# isp_hvp_shield.net
KiCad netlist of a schematic drawn in EAGLE
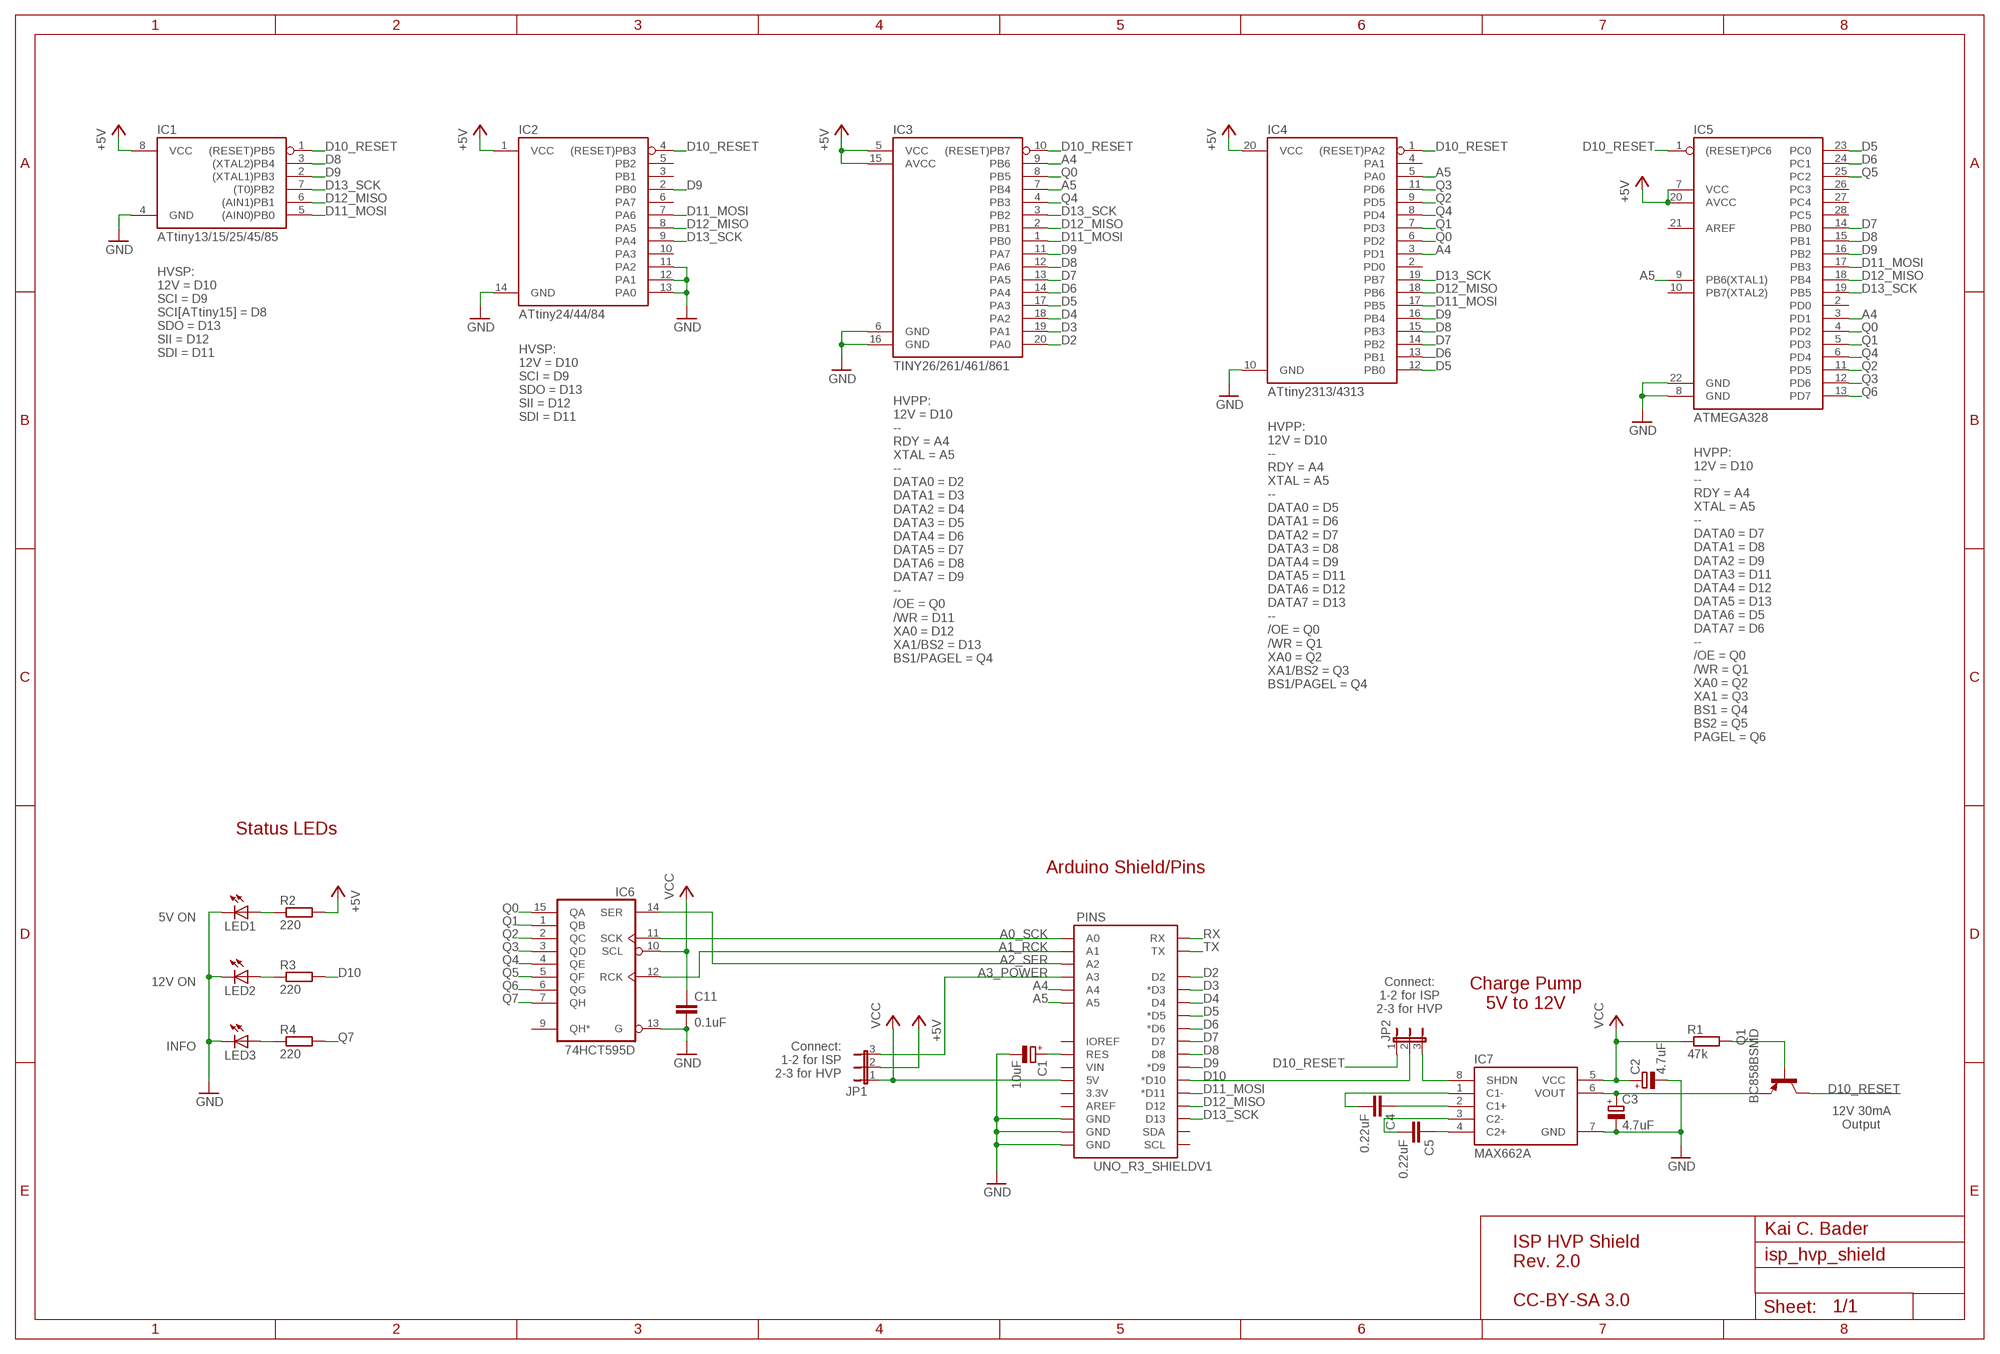
[diagram p0: schematic, sheet 1]

(export (version "E")
  (design (tool "Eeschema 10.0.6"))
  (components
    (comp (ref "C1")
      (value "10uF")
      (footprint "eagle-import:E2-5")
      (libsource (lib "eagle-import") (part "CPOL-EUE2-5"))
    )
    (comp (ref "C2")
      (value "4.7uF")
      (footprint "eagle-import:E2-5")
      (libsource (lib "eagle-import") (part "CPOL-EUE2-5"))
    )
    (comp (ref "C3")
      (value "4.7uF")
      (footprint "eagle-import:E2-5")
      (libsource (lib "eagle-import") (part "CPOL-EUE2-5"))
    )
    (comp (ref "C4")
      (value "0.22uF")
      (footprint "eagle-import:C0805")
      (libsource (lib "eagle-import") (part "C-EUC0805"))
    )
    (comp (ref "C5")
      (value "0.22uF")
      (footprint "eagle-import:C0805")
      (libsource (lib "eagle-import") (part "C-EUC0805"))
    )
    (comp (ref "C11")
      (value "0.1uF")
      (footprint "eagle-import:C0805")
      (libsource (lib "eagle-import") (part "C-EUC0805"))
    )
    (comp (ref "IC1")
      (value "ATtiny13/15/25/45/85")
      (footprint "eagle-import:DIL08")
      (libsource (lib "eagle-import") (part "TINY85P"))
    )
    (comp (ref "IC2")
      (value "ATtiny24/44/84")
      (footprint "eagle-import:DIL14")
      (libsource (lib "eagle-import") (part "TINY84"))
    )
    (comp (ref "IC3")
      (value "TINY26/261/461/861")
      (footprint "eagle-import:DIL20")
      (libsource (lib "eagle-import") (part "TINY26"))
    )
    (comp (ref "IC4")
      (value "ATtiny2313/4313")
      (footprint "eagle-import:DIL20")
      (libsource (lib "eagle-import") (part "TINY2313"))
    )
    (comp (ref "IC5")
      (value "ATMEGA328")
      (footprint "eagle-import:DIL28")
      (libsource (lib "eagle-import") (part "ATMEGA328"))
    )
    (comp (ref "IC6")
      (value "74HCT595D")
      (footprint "eagle-import:SO16")
      (libsource (lib "eagle-import") (part "74595DHCT"))
    )
    (comp (ref "IC7")
      (value "MAX662A")
      (footprint "eagle-import:SO08")
      (libsource (lib "eagle-import") (part "MAX662A"))
    )
    (comp (ref "JP1")
      (value "JP2E")
      (footprint "eagle-import:JP2")
      (libsource (lib "eagle-import") (part "JP2E"))
    )
    (comp (ref "JP2")
      (value "JP2E")
      (footprint "eagle-import:JP2")
      (libsource (lib "eagle-import") (part "JP2E"))
    )
    (comp (ref "LED1")
      (value "LEDCHIPLED_0805")
      (footprint "eagle-import:CHIPLED_0805")
      (libsource (lib "eagle-import") (part "LEDCHIPLED_0805"))
    )
    (comp (ref "LED2")
      (value "LEDCHIPLED_0805")
      (footprint "eagle-import:CHIPLED_0805")
      (libsource (lib "eagle-import") (part "LEDCHIPLED_0805"))
    )
    (comp (ref "LED3")
      (value "LEDCHIPLED_0805")
      (footprint "eagle-import:CHIPLED_0805")
      (libsource (lib "eagle-import") (part "LEDCHIPLED_0805"))
    )
    (comp (ref "PINS")
      (value "UNO_R3_SHIELDV1")
      (footprint "eagle-import:UNO_R3_SHIELD")
      (libsource (lib "eagle-import") (part "UNO_R3_SHIELDV1"))
    )
    (comp (ref "Q1")
      (value "BC858BSMD")
      (footprint "eagle-import:SOT23-BEC")
      (libsource (lib "eagle-import") (part "BC858SMDB"))
    )
    (comp (ref "R1")
      (value "47k")
      (footprint "eagle-import:R0805")
      (libsource (lib "eagle-import") (part "R-EU_R0805"))
    )
    (comp (ref "R2")
      (value "220")
      (footprint "eagle-import:R0805")
      (libsource (lib "eagle-import") (part "R-EU_R0805"))
    )
    (comp (ref "R3")
      (value "220")
      (footprint "eagle-import:R0805")
      (libsource (lib "eagle-import") (part "R-EU_R0805"))
    )
    (comp (ref "R4")
      (value "220")
      (footprint "eagle-import:R0805")
      (libsource (lib "eagle-import") (part "R-EU_R0805"))
    )
  )
  (nets
    (net (code "1") (name "+5V") (class "Default")
      (node (ref "IC1") (pin "8") (pinfunction "VCC_8") (pintype "power_in"))
      (node (ref "IC2") (pin "1") (pinfunction "VCC_1") (pintype "power_in"))
      (node (ref "IC3") (pin "15") (pinfunction "AVCC_15") (pintype "power_in"))
      (node (ref "IC3") (pin "5") (pinfunction "VCC_5") (pintype "power_in"))
      (node (ref "IC4") (pin "20") (pinfunction "VCC_20") (pintype "power_in"))
      (node (ref "IC5") (pin "20") (pinfunction "AVCC_20") (pintype "power_in"))
      (node (ref "IC5") (pin "7") (pinfunction "VCC_7") (pintype "power_in"))
      (node (ref "JP1") (pin "2") (pinfunction "2_2") (pintype "passive"))
      (node (ref "R2") (pin "2") (pinfunction "2_2") (pintype "passive"))
    )
    (net (code "2") (name "/A0_SCK") (class "Default")
      (node (ref "IC6") (pin "11") (pinfunction "SCK_11") (pintype "input"))
      (node (ref "PINS") (pin "A0") (pinfunction "A0_A0") (pintype "bidirectional"))
    )
    (net (code "3") (name "/A1_RCK") (class "Default")
      (node (ref "IC6") (pin "12") (pinfunction "RCK_12") (pintype "input"))
      (node (ref "PINS") (pin "A1") (pinfunction "A1_A1") (pintype "bidirectional"))
    )
    (net (code "4") (name "/A2_SER") (class "Default")
      (node (ref "IC6") (pin "14") (pinfunction "SER_14") (pintype "input"))
      (node (ref "PINS") (pin "A2") (pinfunction "A2_A2") (pintype "bidirectional"))
    )
    (net (code "5") (name "/A3_POWER") (class "Default")
      (node (ref "JP1") (pin "3") (pinfunction "3_3") (pintype "passive"))
      (node (ref "PINS") (pin "A3") (pinfunction "A3_A3") (pintype "bidirectional"))
    )
    (net (code "6") (name "/A4") (class "Default")
      (node (ref "IC3") (pin "9") (pinfunction "PB6_9") (pintype "bidirectional"))
      (node (ref "IC4") (pin "3") (pinfunction "PD1_3") (pintype "bidirectional"))
      (node (ref "IC5") (pin "3") (pinfunction "PD1_3") (pintype "bidirectional"))
      (node (ref "PINS") (pin "A4") (pinfunction "A4_A4") (pintype "bidirectional"))
    )
    (net (code "7") (name "/A5") (class "Default")
      (node (ref "IC3") (pin "7") (pinfunction "PB4_7") (pintype "bidirectional"))
      (node (ref "IC4") (pin "5") (pinfunction "PA0_5") (pintype "bidirectional"))
      (node (ref "IC5") (pin "9") (pinfunction "PB6(XTAL1)_9") (pintype "bidirectional"))
      (node (ref "PINS") (pin "A5") (pinfunction "A5_A5") (pintype "bidirectional"))
    )
    (net (code "8") (name "/AREF") (class "Default")
      (node (ref "IC5") (pin "21") (pinfunction "AREF_21") (pintype "power_in"))
    )
    (net (code "9") (name "/D2") (class "Default")
      (node (ref "IC3") (pin "20") (pinfunction "PA0_20") (pintype "bidirectional"))
      (node (ref "PINS") (pin "D2") (pinfunction "D2_D2") (pintype "bidirectional"))
    )
    (net (code "10") (name "/D3") (class "Default")
      (node (ref "IC3") (pin "19") (pinfunction "PA1_19") (pintype "bidirectional"))
      (node (ref "PINS") (pin "D3") (pinfunction "*D3_D3") (pintype "bidirectional"))
    )
    (net (code "11") (name "/D4") (class "Default")
      (node (ref "IC3") (pin "18") (pinfunction "PA2_18") (pintype "bidirectional"))
      (node (ref "PINS") (pin "D4") (pinfunction "D4_D4") (pintype "bidirectional"))
    )
    (net (code "12") (name "/D5") (class "Default")
      (node (ref "IC3") (pin "17") (pinfunction "PA3_17") (pintype "bidirectional"))
      (node (ref "IC4") (pin "12") (pinfunction "PB0_12") (pintype "bidirectional"))
      (node (ref "IC5") (pin "23") (pinfunction "PC0_23") (pintype "bidirectional"))
      (node (ref "PINS") (pin "D5") (pinfunction "*D5_D5") (pintype "bidirectional"))
    )
    (net (code "13") (name "/D6") (class "Default")
      (node (ref "IC3") (pin "14") (pinfunction "PA4_14") (pintype "bidirectional"))
      (node (ref "IC4") (pin "13") (pinfunction "PB1_13") (pintype "bidirectional"))
      (node (ref "IC5") (pin "24") (pinfunction "PC1_24") (pintype "bidirectional"))
      (node (ref "PINS") (pin "D6") (pinfunction "*D6_D6") (pintype "bidirectional"))
    )
    (net (code "14") (name "/D7") (class "Default")
      (node (ref "IC3") (pin "13") (pinfunction "PA5_13") (pintype "bidirectional"))
      (node (ref "IC4") (pin "14") (pinfunction "PB2_14") (pintype "bidirectional"))
      (node (ref "IC5") (pin "14") (pinfunction "PB0_14") (pintype "bidirectional"))
      (node (ref "PINS") (pin "D7") (pinfunction "D7_D7") (pintype "bidirectional"))
    )
    (net (code "15") (name "/D8") (class "Default")
      (node (ref "IC1") (pin "3") (pinfunction "(XTAL2)PB4_3") (pintype "bidirectional"))
      (node (ref "IC3") (pin "12") (pinfunction "PA6_12") (pintype "bidirectional"))
      (node (ref "IC4") (pin "15") (pinfunction "PB3_15") (pintype "bidirectional"))
      (node (ref "IC5") (pin "15") (pinfunction "PB1_15") (pintype "bidirectional"))
      (node (ref "PINS") (pin "D8") (pinfunction "D8_D8") (pintype "bidirectional"))
    )
    (net (code "16") (name "/D9") (class "Default")
      (node (ref "IC1") (pin "2") (pinfunction "(XTAL1)PB3_2") (pintype "bidirectional"))
      (node (ref "IC2") (pin "2") (pinfunction "PB0_2") (pintype "bidirectional"))
      (node (ref "IC3") (pin "11") (pinfunction "PA7_11") (pintype "bidirectional"))
      (node (ref "IC4") (pin "16") (pinfunction "PB4_16") (pintype "bidirectional"))
      (node (ref "IC5") (pin "16") (pinfunction "PB2_16") (pintype "bidirectional"))
      (node (ref "PINS") (pin "D9") (pinfunction "*D9_D9") (pintype "bidirectional"))
    )
    (net (code "17") (name "/D10") (class "Default")
      (node (ref "JP2") (pin "2") (pinfunction "2_2") (pintype "passive"))
      (node (ref "PINS") (pin "D10") (pinfunction "*D10_D10") (pintype "bidirectional"))
      (node (ref "R3") (pin "2") (pinfunction "2_2") (pintype "passive"))
    )
    (net (code "18") (name "/D10_RESET") (class "Default")
      (node (ref "IC1") (pin "1") (pinfunction "(RESET)PB5_1") (pintype "bidirectional"))
      (node (ref "IC2") (pin "4") (pinfunction "(RESET)PB3_4") (pintype "bidirectional"))
      (node (ref "IC3") (pin "10") (pinfunction "(RESET)PB7_10") (pintype "bidirectional"))
      (node (ref "IC4") (pin "1") (pinfunction "(RESET)PA2_1") (pintype "bidirectional"))
      (node (ref "IC5") (pin "1") (pinfunction "(RESET)PC6_1") (pintype "bidirectional"))
      (node (ref "JP2") (pin "1") (pinfunction "1_1") (pintype "passive"))
      (node (ref "Q1") (pin "C") (pinfunction "C_C") (pintype "passive"))
    )
    (net (code "19") (name "/D11_MOSI") (class "Default")
      (node (ref "IC1") (pin "5") (pinfunction "(AIN0)PB0_5") (pintype "bidirectional"))
      (node (ref "IC2") (pin "7") (pinfunction "PA6_7") (pintype "bidirectional"))
      (node (ref "IC3") (pin "1") (pinfunction "PB0_1") (pintype "bidirectional"))
      (node (ref "IC4") (pin "17") (pinfunction "PB5_17") (pintype "bidirectional"))
      (node (ref "IC5") (pin "17") (pinfunction "PB3_17") (pintype "bidirectional"))
      (node (ref "PINS") (pin "D11") (pinfunction "*D11_D11") (pintype "bidirectional"))
    )
    (net (code "20") (name "/D12_MISO") (class "Default")
      (node (ref "IC1") (pin "6") (pinfunction "(AIN1)PB1_6") (pintype "bidirectional"))
      (node (ref "IC2") (pin "8") (pinfunction "PA5_8") (pintype "bidirectional"))
      (node (ref "IC3") (pin "2") (pinfunction "PB1_2") (pintype "bidirectional"))
      (node (ref "IC4") (pin "18") (pinfunction "PB6_18") (pintype "bidirectional"))
      (node (ref "IC5") (pin "18") (pinfunction "PB4_18") (pintype "bidirectional"))
      (node (ref "PINS") (pin "D12") (pinfunction "D12_D12") (pintype "bidirectional"))
    )
    (net (code "21") (name "/D13_SCK") (class "Default")
      (node (ref "IC1") (pin "7") (pinfunction "(T0)PB2_7") (pintype "bidirectional"))
      (node (ref "IC2") (pin "9") (pinfunction "PA4_9") (pintype "bidirectional"))
      (node (ref "IC3") (pin "3") (pinfunction "PB2_3") (pintype "bidirectional"))
      (node (ref "IC4") (pin "19") (pinfunction "PB7_19") (pintype "bidirectional"))
      (node (ref "IC5") (pin "19") (pinfunction "PB5_19") (pintype "bidirectional"))
      (node (ref "PINS") (pin "D13") (pinfunction "D13_D13") (pintype "bidirectional"))
    )
    (net (code "22") (name "/Q0") (class "Default")
      (node (ref "IC3") (pin "8") (pinfunction "PB5_8") (pintype "bidirectional"))
      (node (ref "IC4") (pin "6") (pinfunction "PD2_6") (pintype "bidirectional"))
      (node (ref "IC5") (pin "4") (pinfunction "PD2_4") (pintype "bidirectional"))
      (node (ref "IC6") (pin "15") (pinfunction "QA_15") (pintype "tri_state"))
    )
    (net (code "23") (name "/Q1") (class "Default")
      (node (ref "IC4") (pin "7") (pinfunction "PD3_7") (pintype "bidirectional"))
      (node (ref "IC5") (pin "5") (pinfunction "PD3_5") (pintype "bidirectional"))
      (node (ref "IC6") (pin "1") (pinfunction "QB_1") (pintype "tri_state"))
    )
    (net (code "24") (name "/Q2") (class "Default")
      (node (ref "IC4") (pin "9") (pinfunction "PD5_9") (pintype "bidirectional"))
      (node (ref "IC5") (pin "11") (pinfunction "PD5_11") (pintype "bidirectional"))
      (node (ref "IC6") (pin "2") (pinfunction "QC_2") (pintype "tri_state"))
    )
    (net (code "25") (name "/Q3") (class "Default")
      (node (ref "IC4") (pin "11") (pinfunction "PD6_11") (pintype "bidirectional"))
      (node (ref "IC5") (pin "12") (pinfunction "PD6_12") (pintype "bidirectional"))
      (node (ref "IC6") (pin "3") (pinfunction "QD_3") (pintype "tri_state"))
    )
    (net (code "26") (name "/Q4") (class "Default")
      (node (ref "IC3") (pin "4") (pinfunction "PB3_4") (pintype "bidirectional"))
      (node (ref "IC4") (pin "8") (pinfunction "PD4_8") (pintype "bidirectional"))
      (node (ref "IC5") (pin "6") (pinfunction "PD4_6") (pintype "bidirectional"))
      (node (ref "IC6") (pin "4") (pinfunction "QE_4") (pintype "tri_state"))
    )
    (net (code "27") (name "/Q5") (class "Default")
      (node (ref "IC5") (pin "25") (pinfunction "PC2_25") (pintype "bidirectional"))
      (node (ref "IC6") (pin "5") (pinfunction "QF_5") (pintype "tri_state"))
    )
    (net (code "28") (name "/Q6") (class "Default")
      (node (ref "IC5") (pin "13") (pinfunction "PD7_13") (pintype "bidirectional"))
      (node (ref "IC6") (pin "6") (pinfunction "QG_6") (pintype "tri_state"))
    )
    (net (code "29") (name "/Q7") (class "Default")
      (node (ref "IC6") (pin "7") (pinfunction "QH_7") (pintype "tri_state"))
      (node (ref "R4") (pin "2") (pinfunction "2_2") (pintype "passive"))
    )
    (net (code "30") (name "/RX") (class "Default")
      (node (ref "PINS") (pin "RX") (pinfunction "RX_RX") (pintype "bidirectional"))
    )
    (net (code "31") (name "/TX") (class "Default")
      (node (ref "PINS") (pin "TX") (pinfunction "TX_TX") (pintype "bidirectional"))
    )
    (net (code "32") (name "GND") (class "Default")
      (node (ref "C1") (pin "-") (pinfunction "-_-") (pintype "passive"))
      (node (ref "C11") (pin "2") (pinfunction "2_2") (pintype "passive"))
      (node (ref "C2") (pin "-") (pinfunction "-_-") (pintype "passive"))
      (node (ref "C3") (pin "-") (pinfunction "-_-") (pintype "passive"))
      (node (ref "IC1") (pin "4") (pinfunction "GND_4") (pintype "power_in"))
      (node (ref "IC2") (pin "11") (pinfunction "PA2_11") (pintype "bidirectional"))
      (node (ref "IC2") (pin "12") (pinfunction "PA1_12") (pintype "bidirectional"))
      (node (ref "IC2") (pin "13") (pinfunction "PA0_13") (pintype "bidirectional"))
      (node (ref "IC2") (pin "14") (pinfunction "GND_14") (pintype "power_in"))
      (node (ref "IC3") (pin "16") (pinfunction "GND_16") (pintype "power_in"))
      (node (ref "IC3") (pin "6") (pinfunction "GND_6") (pintype "power_in"))
      (node (ref "IC4") (pin "10") (pinfunction "GND_10") (pintype "power_in"))
      (node (ref "IC5") (pin "22") (pinfunction "GND_22") (pintype "power_in"))
      (node (ref "IC5") (pin "8") (pinfunction "GND_8") (pintype "power_in"))
      (node (ref "IC6") (pin "13") (pinfunction "G_13") (pintype "input"))
      (node (ref "IC7") (pin "7") (pinfunction "GND_7") (pintype "power_in"))
      (node (ref "LED1") (pin "C") (pinfunction "C_C") (pintype "passive"))
      (node (ref "LED2") (pin "C") (pinfunction "C_C") (pintype "passive"))
      (node (ref "LED3") (pin "C") (pinfunction "C_C") (pintype "passive"))
      (node (ref "PINS") (pin "GND@0") (pinfunction "GND_GND@0") (pintype "bidirectional"))
      (node (ref "PINS") (pin "GND@1") (pinfunction "GND_GND@1") (pintype "bidirectional"))
      (node (ref "PINS") (pin "GND@2") (pinfunction "GND_GND@2") (pintype "bidirectional"))
    )
    (net (code "33") (name "Net-(C1-Pad+)") (class "Default")
      (node (ref "C1") (pin "+") (pinfunction "+_+") (pintype "passive"))
      (node (ref "PINS") (pin "RES") (pinfunction "RES_RES") (pintype "bidirectional"))
    )
    (net (code "34") (name "Net-(IC7-C1+)") (class "Default")
      (node (ref "C4") (pin "1") (pinfunction "1_1") (pintype "passive"))
      (node (ref "IC7") (pin "2") (pinfunction "C1+_2") (pintype "bidirectional"))
    )
    (net (code "35") (name "Net-(IC7-C1-)") (class "Default")
      (node (ref "C4") (pin "2") (pinfunction "2_2") (pintype "passive"))
      (node (ref "IC7") (pin "1") (pinfunction "C1-_1") (pintype "bidirectional"))
    )
    (net (code "36") (name "Net-(IC7-C2+)") (class "Default")
      (node (ref "C5") (pin "1") (pinfunction "1_1") (pintype "passive"))
      (node (ref "IC7") (pin "4") (pinfunction "C2+_4") (pintype "bidirectional"))
    )
    (net (code "37") (name "Net-(IC7-C2-)") (class "Default")
      (node (ref "C5") (pin "2") (pinfunction "2_2") (pintype "passive"))
      (node (ref "IC7") (pin "3") (pinfunction "C2-_3") (pintype "bidirectional"))
    )
    (net (code "38") (name "Net-(IC7-SHDN)") (class "Default")
      (node (ref "IC7") (pin "8") (pinfunction "SHDN_8") (pintype "input"))
      (node (ref "JP2") (pin "3") (pinfunction "3_3") (pintype "passive"))
    )
    (net (code "39") (name "Net-(IC7-VOUT)") (class "Default")
      (node (ref "C3") (pin "+") (pinfunction "+_+") (pintype "passive"))
      (node (ref "IC7") (pin "6") (pinfunction "VOUT_6") (pintype "power_in"))
      (node (ref "Q1") (pin "E") (pinfunction "E_E") (pintype "passive"))
    )
    (net (code "40") (name "Net-(LED1-PadA)") (class "Default")
      (node (ref "LED1") (pin "A") (pinfunction "A_A") (pintype "passive"))
      (node (ref "R2") (pin "1") (pinfunction "1_1") (pintype "passive"))
    )
    (net (code "41") (name "Net-(LED2-PadA)") (class "Default")
      (node (ref "LED2") (pin "A") (pinfunction "A_A") (pintype "passive"))
      (node (ref "R3") (pin "1") (pinfunction "1_1") (pintype "passive"))
    )
    (net (code "42") (name "Net-(LED3-PadA)") (class "Default")
      (node (ref "LED3") (pin "A") (pinfunction "A_A") (pintype "passive"))
      (node (ref "R4") (pin "1") (pinfunction "1_1") (pintype "passive"))
    )
    (net (code "43") (name "Net-(Q1-PadB)") (class "Default")
      (node (ref "Q1") (pin "B") (pinfunction "B_B") (pintype "passive"))
      (node (ref "R1") (pin "2") (pinfunction "2_2") (pintype "passive"))
    )
    (net (code "44") (name "VCC") (class "Default")
      (node (ref "C11") (pin "1") (pinfunction "1_1") (pintype "passive"))
      (node (ref "C2") (pin "+") (pinfunction "+_+") (pintype "passive"))
      (node (ref "IC6") (pin "10") (pinfunction "SCL_10") (pintype "input"))
      (node (ref "IC7") (pin "5") (pinfunction "VCC_5") (pintype "power_in"))
      (node (ref "JP1") (pin "1") (pinfunction "1_1") (pintype "passive"))
      (node (ref "PINS") (pin "5V") (pinfunction "5V_5V") (pintype "bidirectional"))
      (node (ref "R1") (pin "1") (pinfunction "1_1") (pintype "passive"))
    )
    (net (code "45") (name "unconnected-(IC2-PA3-Pad10)") (class "Default")
      (node (ref "IC2") (pin "10") (pinfunction "PA3_10") (pintype "bidirectional"))
    )
    (net (code "46") (name "unconnected-(IC2-PA7-Pad6)") (class "Default")
      (node (ref "IC2") (pin "6") (pinfunction "PA7_6") (pintype "bidirectional"))
    )
    (net (code "47") (name "unconnected-(IC2-PB1-Pad3)") (class "Default")
      (node (ref "IC2") (pin "3") (pinfunction "PB1_3") (pintype "bidirectional"))
    )
    (net (code "48") (name "unconnected-(IC2-PB2-Pad5)") (class "Default")
      (node (ref "IC2") (pin "5") (pinfunction "PB2_5") (pintype "bidirectional"))
    )
    (net (code "49") (name "unconnected-(IC4-PA1-Pad4)") (class "Default")
      (node (ref "IC4") (pin "4") (pinfunction "PA1_4") (pintype "bidirectional"))
    )
    (net (code "50") (name "unconnected-(IC4-PD0-Pad2)") (class "Default")
      (node (ref "IC4") (pin "2") (pinfunction "PD0_2") (pintype "bidirectional"))
    )
    (net (code "51") (name "unconnected-(IC5-PB7(XTAL2)-Pad10)") (class "Default")
      (node (ref "IC5") (pin "10") (pinfunction "PB7(XTAL2)_10") (pintype "bidirectional"))
    )
    (net (code "52") (name "unconnected-(IC5-PC3-Pad26)") (class "Default")
      (node (ref "IC5") (pin "26") (pinfunction "PC3_26") (pintype "bidirectional"))
    )
    (net (code "53") (name "unconnected-(IC5-PC4-Pad27)") (class "Default")
      (node (ref "IC5") (pin "27") (pinfunction "PC4_27") (pintype "bidirectional"))
    )
    (net (code "54") (name "unconnected-(IC5-PC5-Pad28)") (class "Default")
      (node (ref "IC5") (pin "28") (pinfunction "PC5_28") (pintype "bidirectional"))
    )
    (net (code "55") (name "unconnected-(IC5-PD0-Pad2)") (class "Default")
      (node (ref "IC5") (pin "2") (pinfunction "PD0_2") (pintype "bidirectional"))
    )
    (net (code "56") (name "unconnected-(IC6A-QH*-Pad9)") (class "Default")
      (node (ref "IC6") (pin "9") (pinfunction "QH*_9") (pintype "tri_state"))
    )
    (net (code "57") (name "unconnected-(PINS-Pad3.3V)") (class "Default")
      (node (ref "PINS") (pin "3.3V") (pinfunction "3.3V_3.3V") (pintype "bidirectional"))
    )
    (net (code "58") (name "unconnected-(PINS-PadAREF)") (class "Default")
      (node (ref "PINS") (pin "AREF") (pinfunction "AREF_AREF") (pintype "bidirectional"))
    )
    (net (code "59") (name "unconnected-(PINS-PadIOREF)") (class "Default")
      (node (ref "PINS") (pin "IOREF") (pinfunction "IOREF_IOREF") (pintype "bidirectional"))
    )
    (net (code "60") (name "unconnected-(PINS-PadSCL)") (class "Default")
      (node (ref "PINS") (pin "SCL") (pinfunction "SCL_SCL") (pintype "bidirectional"))
    )
    (net (code "61") (name "unconnected-(PINS-PadSDA)") (class "Default")
      (node (ref "PINS") (pin "SDA") (pinfunction "SDA_SDA") (pintype "bidirectional"))
    )
    (net (code "62") (name "unconnected-(PINS-PadVIN)") (class "Default")
      (node (ref "PINS") (pin "VIN") (pinfunction "VIN_VIN") (pintype "bidirectional"))
    )
  )
)
